# POEActiveTransformer.net
KiCad netlist of a schematic drawn in Altium Designer
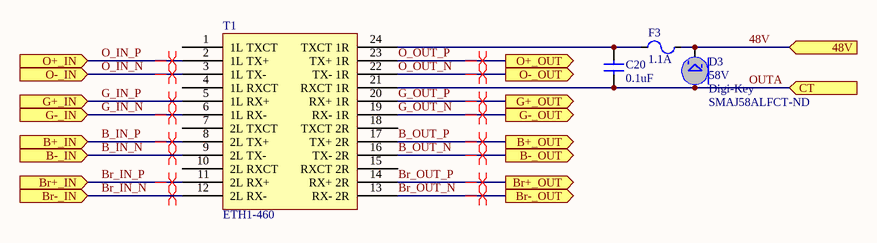
[diagram p0: POEActiveTransformer.SchDoc]

(export (version "E")
  (design (tool "Eeschema 10.0.6"))
  (components
    (comp (ref "C20")
      (value "0.1uF")
      (footprint "CAPC0603")
      (fields (field (name "Comment") "Cap"))
      (libsource (lib "Passives") (part "Cap"))
    )
    (comp (ref "D3")
      (value "58V")
      (footprint "SMASeries")
      (description "Zener Diode")
      (fields
        (field (name "SUPPLIER 1") "Digi-Key")
        (field (name "SUPPLIER PART NUMBER 1") "SMAJ58ALFCT-ND")
        (field (name "Comment") "Zener")
      )
      (libsource (lib "Semiconductors") (part "Zener"))
    )
    (comp (ref "F3")
      (value "1.1A")
      (footprint "PTC7451X11N")
      (fields (field (name "Comment") "PTC Fuse"))
      (libsource (lib "Passives") (part "PTC_Fuse"))
    )
    (comp (ref "T1")
      (value "ETH1-460")
      (footprint "ETH1-460")
      (description "\"PoE Plus\" Transformers Audio & Signal ETH1 60W 4pairs PoE+ Magnetic Module")
      (libsource (lib "ICs") (part "ETH1-460"))
    )
  )
  (nets
    (net (code "1") (name "/48V") (class "Default")
      (node (ref "D3") (pin "C") (pinfunction "C_C") (pintype "passive"))
      (node (ref "F3") (pin "2") (pinfunction "B_2") (pintype "passive"))
    )
    (net (code "2") (name "/B_IN_N") (class "Default")
      (node (ref "T1") (pin "9") (pinfunction "2L_TX-_9") (pintype "passive"))
    )
    (net (code "3") (name "/B_IN_P") (class "Default")
      (node (ref "T1") (pin "8") (pinfunction "2L_TX+_8") (pintype "passive"))
    )
    (net (code "4") (name "/B_OUT_N") (class "Default")
      (node (ref "T1") (pin "16") (pinfunction "TX-_2R_16") (pintype "passive"))
    )
    (net (code "5") (name "/B_OUT_P") (class "Default")
      (node (ref "T1") (pin "17") (pinfunction "TX+_2R_17") (pintype "passive"))
    )
    (net (code "6") (name "/Br_IN_N") (class "Default")
      (node (ref "T1") (pin "12") (pinfunction "2L_RX-_12") (pintype "passive"))
    )
    (net (code "7") (name "/Br_IN_P") (class "Default")
      (node (ref "T1") (pin "11") (pinfunction "2L_RX+_11") (pintype "passive"))
    )
    (net (code "8") (name "/Br_OUT_N") (class "Default")
      (node (ref "T1") (pin "13") (pinfunction "RX-_2R_13") (pintype "passive"))
    )
    (net (code "9") (name "/Br_OUT_P") (class "Default")
      (node (ref "T1") (pin "14") (pinfunction "RX+_2R_14") (pintype "passive"))
    )
    (net (code "10") (name "/G_IN_N") (class "Default")
      (node (ref "T1") (pin "6") (pinfunction "1L_RX-_6") (pintype "passive"))
    )
    (net (code "11") (name "/G_IN_P") (class "Default")
      (node (ref "T1") (pin "5") (pinfunction "1L_RX+_5") (pintype "passive"))
    )
    (net (code "12") (name "/G_OUT_N") (class "Default")
      (node (ref "T1") (pin "19") (pinfunction "RX-_1R_19") (pintype "passive"))
    )
    (net (code "13") (name "/G_OUT_P") (class "Default")
      (node (ref "T1") (pin "20") (pinfunction "RX+_1R_20") (pintype "passive"))
    )
    (net (code "14") (name "/OUTA") (class "Default")
      (node (ref "C20") (pin "2") (pinfunction "B_2") (pintype "passive"))
      (node (ref "D3") (pin "A") (pinfunction "A_A") (pintype "passive"))
      (node (ref "T1") (pin "21") (pinfunction "RXCT_1R_21") (pintype "passive"))
    )
    (net (code "15") (name "/O_IN_N") (class "Default")
      (node (ref "T1") (pin "3") (pinfunction "1L_TX-_3") (pintype "passive"))
    )
    (net (code "16") (name "/O_IN_P") (class "Default")
      (node (ref "T1") (pin "2") (pinfunction "1L_TX+_2") (pintype "passive"))
    )
    (net (code "17") (name "/O_OUT_N") (class "Default")
      (node (ref "T1") (pin "22") (pinfunction "TX-_1R_22") (pintype "passive"))
    )
    (net (code "18") (name "/O_OUT_P") (class "Default")
      (node (ref "T1") (pin "23") (pinfunction "TX+_1R_23") (pintype "passive"))
    )
    (net (code "19") (name "Net-(C20-A)") (class "Default")
      (node (ref "C20") (pin "1") (pinfunction "A_1") (pintype "passive"))
      (node (ref "F3") (pin "1") (pinfunction "A_1") (pintype "passive"))
      (node (ref "T1") (pin "24") (pinfunction "TXCT_1R_24") (pintype "passive"))
    )
    (net (code "20") (name "unconnected-(T1-1L_RXCT-Pad4)") (class "Default")
      (node (ref "T1") (pin "4") (pinfunction "1L_RXCT_4") (pintype "passive"))
    )
    (net (code "21") (name "unconnected-(T1-1L_TXCT-Pad1)") (class "Default")
      (node (ref "T1") (pin "1") (pinfunction "1L_TXCT_1") (pintype "passive"))
    )
    (net (code "22") (name "unconnected-(T1-2L_RXCT-Pad10)") (class "Default")
      (node (ref "T1") (pin "10") (pinfunction "2L_RXCT_10") (pintype "passive"))
    )
    (net (code "23") (name "unconnected-(T1-2L_TXCT-Pad7)") (class "Default")
      (node (ref "T1") (pin "7") (pinfunction "2L_TXCT_7") (pintype "passive"))
    )
    (net (code "24") (name "unconnected-(T1-RXCT_2R-Pad15)") (class "Default")
      (node (ref "T1") (pin "15") (pinfunction "RXCT_2R_15") (pintype "passive"))
    )
    (net (code "25") (name "unconnected-(T1-TXCT_2R-Pad18)") (class "Default")
      (node (ref "T1") (pin "18") (pinfunction "TXCT_2R_18") (pintype "passive"))
    )
  )
)
